# MCU.net
KiCad netlist of a schematic drawn in Altium Designer
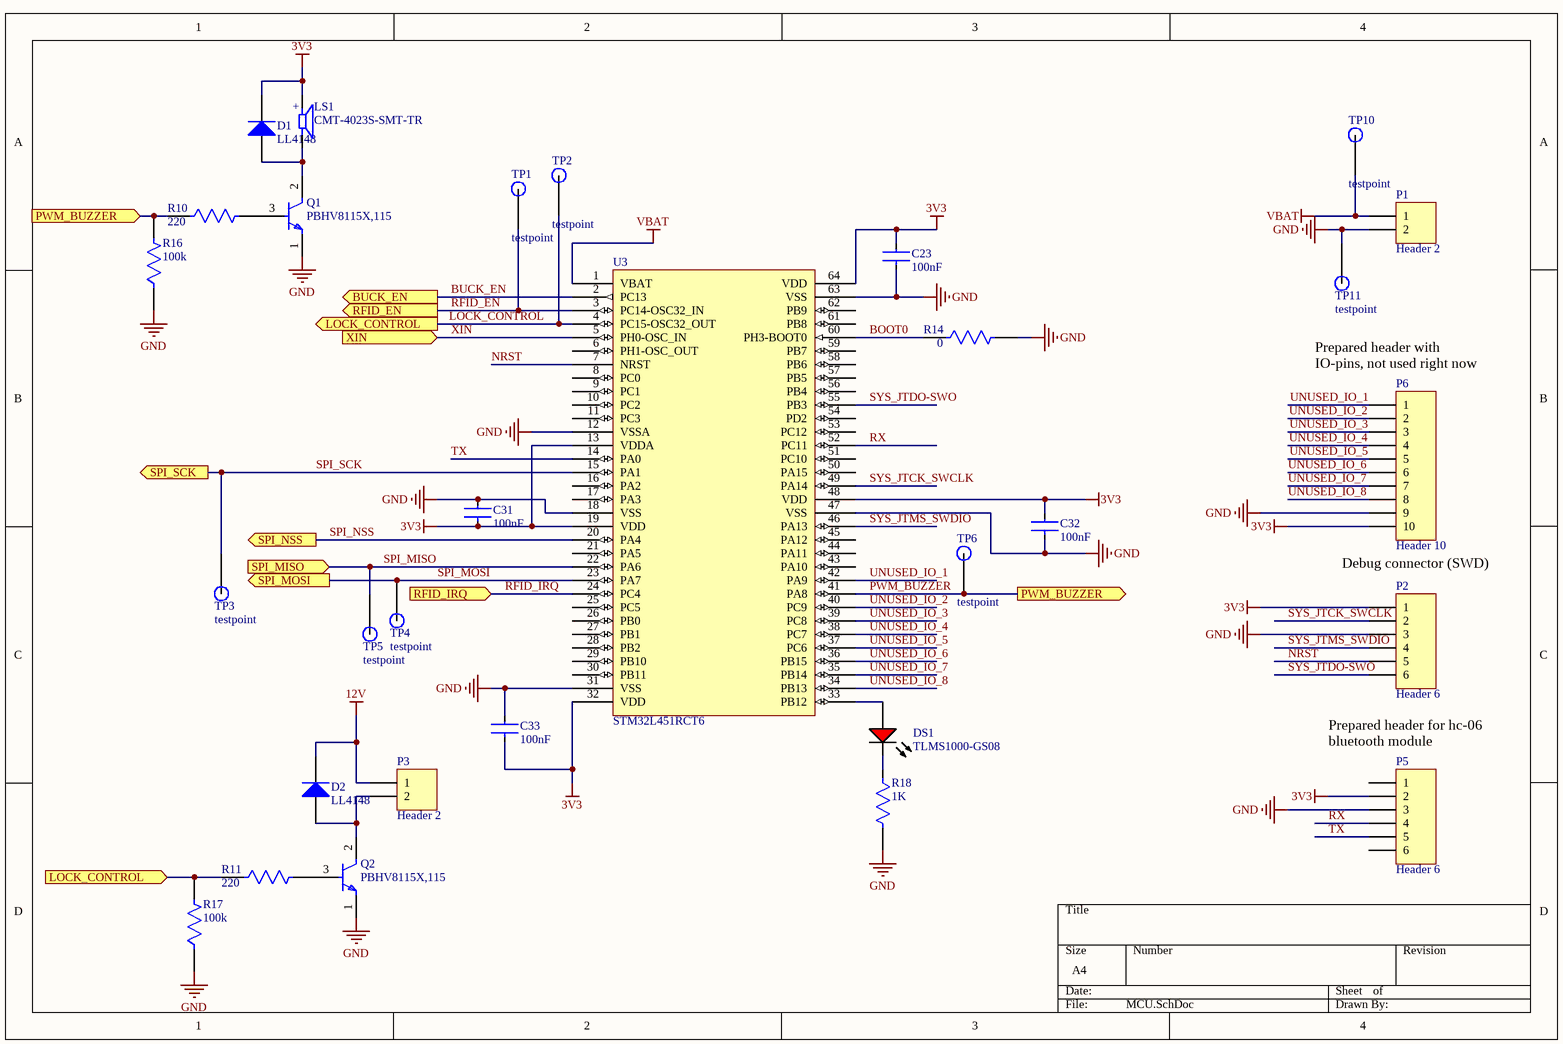
[diagram p0: MCU.SchDoc]

(export (version "E")
  (design (tool "Eeschema 10.0.6"))
  (components
    (comp (ref "C23")
      (value "100nF")
      (footprint "FP-GCJ21B-0_3-IPC_A")
      (description "Multilayer Ceramic Capacitors MLCC - SMD/SMT 0805 2.2uF 10%, 16VDC,  X7R 15%")
      (fields (field (name "TOLERANCE") "10%"))
      (libsource (lib "Altium Content Vault") (part "02cd4be3c70576c341d710602a673aa"))
    )
    (comp (ref "C31")
      (value "100nF")
      (footprint "FP-GCJ21B-0_3-IPC_A")
      (description "Multilayer Ceramic Capacitors MLCC - SMD/SMT 0805 2.2uF 10%, 16VDC,  X7R 15%")
      (fields (field (name "TOLERANCE") "10%"))
      (libsource (lib "Altium Content Vault") (part "02cd4be3c70576c341d710602a673aa"))
    )
    (comp (ref "C32")
      (value "100nF")
      (footprint "FP-GCJ21B-0_3-IPC_A")
      (description "Multilayer Ceramic Capacitors MLCC - SMD/SMT 0805 2.2uF 10%, 16VDC,  X7R 15%")
      (fields (field (name "TOLERANCE") "10%"))
      (libsource (lib "Altium Content Vault") (part "02cd4be3c70576c341d710602a673aa"))
    )
    (comp (ref "C33")
      (value "100nF")
      (footprint "FP-GCJ21B-0_3-IPC_A")
      (description "Multilayer Ceramic Capacitors MLCC - SMD/SMT 0805 2.2uF 10%, 16VDC,  X7R 15%")
      (fields (field (name "TOLERANCE") "10%"))
      (libsource (lib "Altium Content Vault") (part "02cd4be3c70576c341d710602a673aa"))
    )
    (comp (ref "D1")
      (value "LL4148")
      (footprint "FAIR-SOD80-2_V")
      (description "Small Signal Diode, 100 V, 0.2 A, -55 to 175 degC, 2-Pin SOD80, RoHS, Tape and Reel")
      (fields (field (name "MANUFACTURER") "Fairchild"))
      (libsource (lib "Altium Content Vault") (part "D-AK-2"))
    )
    (comp (ref "D2")
      (value "LL4148")
      (footprint "FAIR-SOD80-2_V")
      (description "Small Signal Diode, 100 V, 0.2 A, -55 to 175 degC, 2-Pin SOD80, RoHS, Tape and Reel")
      (fields (field (name "MANUFACTURER") "Fairchild"))
      (libsource (lib "Altium Content Vault") (part "D-AK-2"))
    )
    (comp (ref "DS1")
      (value "TLMS1000-GS08")
      (footprint "VISH-TLMS1000_V")
      (description "Low Current LED, 40 mW, 1.8 V, -40 to 100 degC, 2-Pin SMD (0603), RoHS, Tape and Reel")
      (fields (field (name "MANUFACTURER") "Vishay"))
      (libsource (lib "Altium Content Vault") (part "LED-RED-AK-2"))
    )
    (comp (ref "LS1")
      (value "CMT-4023S-SMT-TR")
      (footprint "CUI_CMT-4023S-SMT-TR")
      (description "4 mm, 3 Vo-p, 70 dB, Surface Mount _SMT_, Magnetic Audio Transducer Buzzer")
      (fields (field (name "MF") "CUI Devices"))
      (libsource (lib "Schlib") (part "CMT-4023S-SMT-TR"))
    )
    (comp (ref "P1")
      (value "Header 2")
      (footprint "HDR1X2")
      (description "Header, 2-Pin")
      (fields (field (name "PUBLISHER") "Altium Limited"))
      (libsource (lib "Miscellaneous Connectors") (part "Header 2"))
    )
    (comp (ref "P2")
      (value "Header 6")
      (footprint "HDR1X6")
      (description "Header, 6-Pin")
      (fields (field (name "PUBLISHER") "Altium Limited"))
      (libsource (lib "Miscellaneous Connectors") (part "Header 6"))
    )
    (comp (ref "P3")
      (value "Header 2")
      (footprint "HDR1X2")
      (description "Header, 2-Pin")
      (fields (field (name "PUBLISHER") "Altium Limited"))
      (libsource (lib "Miscellaneous Connectors") (part "Header 2"))
    )
    (comp (ref "P5")
      (value "Header 6")
      (footprint "HDR1X6")
      (description "Header, 6-Pin")
      (fields (field (name "PUBLISHER") "Altium Limited"))
      (libsource (lib "Miscellaneous Connectors") (part "Header 6"))
    )
    (comp (ref "P6")
      (value "Header 10")
      (footprint "HDR1X10")
      (description "Header, 10-Pin")
      (fields (field (name "PUBLISHER") "Altium Limited"))
      (libsource (lib "Miscellaneous Connectors") (part "Header 10"))
    )
    (comp (ref "Q1")
      (value "PBHV8115X,115")
      (footprint "FP-SOT89-MFG")
      (description "TRANS NPN 150V 1A SOT89")
      (fields
        (field (name "MANUFACTURER") "Nexperia")
        (field (name "OCTOPART") "https://octopart.com/pbhv8115x%2C115-nexperia-78740688")
      )
      (libsource (lib "Altium Content Vault") (part "22d2bcc0fe72a7c4622b2c6aaace23d"))
    )
    (comp (ref "Q2")
      (value "PBHV8115X,115")
      (footprint "FP-SOT89-MFG")
      (description "TRANS NPN 150V 1A SOT89")
      (fields
        (field (name "MANUFACTURER") "Nexperia")
        (field (name "OCTOPART") "https://octopart.com/pbhv8115x%2C115-nexperia-78740688")
      )
      (libsource (lib "Altium Content Vault") (part "22d2bcc0fe72a7c4622b2c6aaace23d"))
    )
    (comp (ref "R10")
      (value "220")
      (footprint "FP-AC0603-MFG")
      (description "RES SMD 60.4 OHM 1% 1/10W 0603")
      (fields
        (field (name "MANUFACTURER PART NUMBER") "AC0603FR-0760R4L")
        (field (name "OCTOPART") "https://octopart.com/ac0603fr-0760r4l-yageo-71367350")
      )
      (libsource (lib "Altium Content Vault") (part "1029c3af85768c4190bb7ad29bc67b5"))
    )
    (comp (ref "R11")
      (value "220")
      (footprint "FP-AC0603-MFG")
      (description "RES SMD 60.4 OHM 1% 1/10W 0603")
      (fields
        (field (name "MANUFACTURER PART NUMBER") "AC0603FR-0760R4L")
        (field (name "OCTOPART") "https://octopart.com/ac0603fr-0760r4l-yageo-71367350")
      )
      (libsource (lib "Altium Content Vault") (part "1029c3af85768c4190bb7ad29bc67b5"))
    )
    (comp (ref "R14")
      (value "0")
      (footprint "FP-AC0603-MFG")
      (description "RES SMD 60.4 OHM 1% 1/10W 0603")
      (fields
        (field (name "MANUFACTURER PART NUMBER") "AC0603FR-0760R4L")
        (field (name "OCTOPART") "https://octopart.com/ac0603fr-0760r4l-yageo-71367350")
      )
      (libsource (lib "Altium Content Vault") (part "1029c3af85768c4190bb7ad29bc67b5"))
    )
    (comp (ref "R16")
      (value "100k")
      (footprint "FP-AC0603-MFG")
      (description "RES SMD 60.4 OHM 1% 1/10W 0603")
      (fields
        (field (name "MANUFACTURER PART NUMBER") "AC0603FR-0760R4L")
        (field (name "OCTOPART") "https://octopart.com/ac0603fr-0760r4l-yageo-71367350")
      )
      (libsource (lib "Altium Content Vault") (part "1029c3af85768c4190bb7ad29bc67b5"))
    )
    (comp (ref "R17")
      (value "100k")
      (footprint "FP-AC0603-MFG")
      (description "RES SMD 60.4 OHM 1% 1/10W 0603")
      (fields
        (field (name "MANUFACTURER PART NUMBER") "AC0603FR-0760R4L")
        (field (name "OCTOPART") "https://octopart.com/ac0603fr-0760r4l-yageo-71367350")
      )
      (libsource (lib "Altium Content Vault") (part "1029c3af85768c4190bb7ad29bc67b5"))
    )
    (comp (ref "R18")
      (value "1K")
      (footprint "FP-AC0603-MFG")
      (description "RES SMD 60.4 OHM 1% 1/10W 0603")
      (fields
        (field (name "MANUFACTURER PART NUMBER") "AC0603FR-0760R4L")
        (field (name "OCTOPART") "https://octopart.com/ac0603fr-0760r4l-yageo-71367350")
      )
      (libsource (lib "Altium Content Vault") (part "1029c3af85768c4190bb7ad29bc67b5"))
    )
    (comp (ref "TP1")
      (value "testpoint")
      (footprint "Testpoint")
      (libsource (lib "Schlib") (part "testpoint"))
    )
    (comp (ref "TP2")
      (value "testpoint")
      (footprint "Testpoint")
      (libsource (lib "Schlib") (part "testpoint"))
    )
    (comp (ref "TP3")
      (value "testpoint")
      (footprint "Testpoint")
      (libsource (lib "Schlib") (part "testpoint"))
    )
    (comp (ref "TP4")
      (value "testpoint")
      (footprint "Testpoint")
      (libsource (lib "Schlib") (part "testpoint"))
    )
    (comp (ref "TP5")
      (value "testpoint")
      (footprint "Testpoint")
      (libsource (lib "Schlib") (part "testpoint"))
    )
    (comp (ref "TP6")
      (value "testpoint")
      (footprint "Testpoint")
      (libsource (lib "Schlib") (part "testpoint"))
    )
    (comp (ref "TP10")
      (value "testpoint")
      (footprint "Testpoint")
      (libsource (lib "Schlib") (part "testpoint"))
    )
    (comp (ref "TP11")
      (value "testpoint")
      (footprint "Testpoint")
      (libsource (lib "Schlib") (part "testpoint"))
    )
    (comp (ref "U3")
      (value "STM32L451RCT6")
      (footprint "LQFP-64")
      (description "MCU 32-bit STM32")
      (fields (field (name "MANUFACTURER") "STMicroelectronics"))
      (libsource (lib "Schlib") (part "STM32L451RCT6"))
    )
  )
  (nets
    (net (code "1") (name "/BOOT0") (class "Default")
      (node (ref "R14") (pin "1") (pinfunction "1_1") (pintype "passive"))
      (node (ref "U3") (pin "60") (pinfunction "PH3-BOOT0_60") (pintype "input"))
    )
    (net (code "2") (name "/BUCK_EN") (class "Default")
      (node (ref "U3") (pin "2") (pinfunction "PC13_2") (pintype "output"))
    )
    (net (code "3") (name "/LOCK_CONTROL") (class "Default")
      (node (ref "R11") (pin "1") (pinfunction "1_1") (pintype "passive"))
      (node (ref "R17") (pin "2") (pinfunction "2_2") (pintype "passive"))
      (node (ref "TP2") (pin "1") (pinfunction "tp_1") (pintype "passive"))
      (node (ref "U3") (pin "4") (pinfunction "PC15-OSC32_OUT_4") (pintype "bidirectional"))
    )
    (net (code "4") (name "/NRST") (class "Default")
      (node (ref "P2") (pin "5") (pinfunction "5_5") (pintype "passive"))
      (node (ref "U3") (pin "7") (pinfunction "NRST_7") (pintype "passive"))
    )
    (net (code "5") (name "/PWM_BUZZER") (class "Default")
      (node (ref "R10") (pin "1") (pinfunction "1_1") (pintype "passive"))
      (node (ref "R16") (pin "2") (pinfunction "2_2") (pintype "passive"))
      (node (ref "TP6") (pin "1") (pinfunction "tp_1") (pintype "passive"))
      (node (ref "U3") (pin "41") (pinfunction "PA8_41") (pintype "bidirectional"))
    )
    (net (code "6") (name "/RFID_EN") (class "Default")
      (node (ref "TP1") (pin "1") (pinfunction "tp_1") (pintype "passive"))
      (node (ref "U3") (pin "3") (pinfunction "PC14-OSC32_IN_3") (pintype "bidirectional"))
    )
    (net (code "7") (name "/RFID_IRQ") (class "Default")
      (node (ref "U3") (pin "24") (pinfunction "PC4_24") (pintype "bidirectional"))
    )
    (net (code "8") (name "/RX") (class "Default")
      (node (ref "P5") (pin "4") (pinfunction "4_4") (pintype "passive"))
      (node (ref "U3") (pin "52") (pinfunction "PC11_52") (pintype "bidirectional"))
    )
    (net (code "9") (name "/SPI_MISO") (class "Default")
      (node (ref "TP5") (pin "1") (pinfunction "tp_1") (pintype "passive"))
      (node (ref "U3") (pin "22") (pinfunction "PA6_22") (pintype "bidirectional"))
    )
    (net (code "10") (name "/SPI_MOSI") (class "Default")
      (node (ref "TP4") (pin "1") (pinfunction "tp_1") (pintype "passive"))
      (node (ref "U3") (pin "23") (pinfunction "PA7_23") (pintype "bidirectional"))
    )
    (net (code "11") (name "/SPI_NSS") (class "Default")
      (node (ref "U3") (pin "20") (pinfunction "PA4_20") (pintype "bidirectional"))
    )
    (net (code "12") (name "/SPI_SCK") (class "Default")
      (node (ref "TP3") (pin "1") (pinfunction "tp_1") (pintype "passive"))
      (node (ref "U3") (pin "15") (pinfunction "PA1_15") (pintype "bidirectional"))
    )
    (net (code "13") (name "/SYS_JTCK_SWCLK") (class "Default")
      (node (ref "P2") (pin "2") (pinfunction "2_2") (pintype "passive"))
      (node (ref "U3") (pin "49") (pinfunction "PA14_49") (pintype "bidirectional"))
    )
    (net (code "14") (name "/SYS_JTDO-SWO") (class "Default")
      (node (ref "P2") (pin "6") (pinfunction "6_6") (pintype "passive"))
      (node (ref "U3") (pin "55") (pinfunction "PB3_55") (pintype "bidirectional"))
    )
    (net (code "15") (name "/SYS_JTMS_SWDIO") (class "Default")
      (node (ref "P2") (pin "4") (pinfunction "4_4") (pintype "passive"))
      (node (ref "U3") (pin "46") (pinfunction "PA13_46") (pintype "bidirectional"))
    )
    (net (code "16") (name "/TX") (class "Default")
      (node (ref "P5") (pin "5") (pinfunction "5_5") (pintype "passive"))
      (node (ref "U3") (pin "14") (pinfunction "PA0_14") (pintype "bidirectional"))
    )
    (net (code "17") (name "/UNUSED_IO_1") (class "Default")
      (node (ref "P6") (pin "1") (pinfunction "1_1") (pintype "passive"))
      (node (ref "U3") (pin "42") (pinfunction "PA9_42") (pintype "bidirectional"))
    )
    (net (code "18") (name "/UNUSED_IO_2") (class "Default")
      (node (ref "P6") (pin "2") (pinfunction "2_2") (pintype "passive"))
      (node (ref "U3") (pin "40") (pinfunction "PC9_40") (pintype "bidirectional"))
    )
    (net (code "19") (name "/UNUSED_IO_3") (class "Default")
      (node (ref "P6") (pin "3") (pinfunction "3_3") (pintype "passive"))
      (node (ref "U3") (pin "39") (pinfunction "PC8_39") (pintype "bidirectional"))
    )
    (net (code "20") (name "/UNUSED_IO_4") (class "Default")
      (node (ref "P6") (pin "4") (pinfunction "4_4") (pintype "passive"))
      (node (ref "U3") (pin "38") (pinfunction "PC7_38") (pintype "bidirectional"))
    )
    (net (code "21") (name "/UNUSED_IO_5") (class "Default")
      (node (ref "P6") (pin "5") (pinfunction "5_5") (pintype "passive"))
      (node (ref "U3") (pin "37") (pinfunction "PC6_37") (pintype "bidirectional"))
    )
    (net (code "22") (name "/UNUSED_IO_6") (class "Default")
      (node (ref "P6") (pin "6") (pinfunction "6_6") (pintype "passive"))
      (node (ref "U3") (pin "36") (pinfunction "PB15_36") (pintype "bidirectional"))
    )
    (net (code "23") (name "/UNUSED_IO_7") (class "Default")
      (node (ref "P6") (pin "7") (pinfunction "7_7") (pintype "passive"))
      (node (ref "U3") (pin "35") (pinfunction "PB14_35") (pintype "bidirectional"))
    )
    (net (code "24") (name "/UNUSED_IO_8") (class "Default")
      (node (ref "P6") (pin "8") (pinfunction "8_8") (pintype "passive"))
      (node (ref "U3") (pin "34") (pinfunction "PB13_34") (pintype "bidirectional"))
    )
    (net (code "25") (name "/XIN") (class "Default")
      (node (ref "U3") (pin "5") (pinfunction "PH0-OSC_IN_5") (pintype "bidirectional"))
    )
    (net (code "26") (name "3V3") (class "Default")
      (node (ref "C23") (pin "2") (pinfunction "2_2") (pintype "passive"))
      (node (ref "C31") (pin "1") (pinfunction "1_1") (pintype "passive"))
      (node (ref "C32") (pin "2") (pinfunction "2_2") (pintype "passive"))
      (node (ref "C33") (pin "1") (pinfunction "1_1") (pintype "passive"))
      (node (ref "D1") (pin "2") (pinfunction "K_2") (pintype "passive"))
      (node (ref "LS1") (pin "P") (pinfunction "P_P") (pintype "passive"))
      (node (ref "P2") (pin "1") (pinfunction "1_1") (pintype "passive"))
      (node (ref "P5") (pin "2") (pinfunction "2_2") (pintype "passive"))
      (node (ref "P6") (pin "10") (pinfunction "10_10") (pintype "passive"))
      (node (ref "U3") (pin "13") (pinfunction "VDDA_13") (pintype "power_in"))
      (node (ref "U3") (pin "19") (pinfunction "VDD_19") (pintype "power_in"))
      (node (ref "U3") (pin "32") (pinfunction "VDD_32") (pintype "power_in"))
      (node (ref "U3") (pin "48") (pinfunction "VDD_48") (pintype "power_in"))
      (node (ref "U3") (pin "64") (pinfunction "VDD_64") (pintype "power_in"))
    )
    (net (code "27") (name "12V") (class "Default")
      (node (ref "D2") (pin "2") (pinfunction "K_2") (pintype "passive"))
      (node (ref "P3") (pin "1") (pinfunction "1_1") (pintype "passive"))
    )
    (net (code "28") (name "GND") (class "Default")
      (node (ref "C23") (pin "1") (pinfunction "1_1") (pintype "passive"))
      (node (ref "C31") (pin "2") (pinfunction "2_2") (pintype "passive"))
      (node (ref "C32") (pin "1") (pinfunction "1_1") (pintype "passive"))
      (node (ref "C33") (pin "2") (pinfunction "2_2") (pintype "passive"))
      (node (ref "P1") (pin "2") (pinfunction "2_2") (pintype "passive"))
      (node (ref "P2") (pin "3") (pinfunction "3_3") (pintype "passive"))
      (node (ref "P5") (pin "3") (pinfunction "3_3") (pintype "passive"))
      (node (ref "P6") (pin "9") (pinfunction "9_9") (pintype "passive"))
      (node (ref "Q1") (pin "1") (pinfunction "E_1") (pintype "passive"))
      (node (ref "Q2") (pin "1") (pinfunction "E_1") (pintype "passive"))
      (node (ref "R14") (pin "2") (pinfunction "2_2") (pintype "passive"))
      (node (ref "R16") (pin "1") (pinfunction "1_1") (pintype "passive"))
      (node (ref "R17") (pin "1") (pinfunction "1_1") (pintype "passive"))
      (node (ref "R18") (pin "2") (pinfunction "2_2") (pintype "passive"))
      (node (ref "TP11") (pin "1") (pinfunction "tp_1") (pintype "passive"))
      (node (ref "U3") (pin "12") (pinfunction "VSSA_12") (pintype "power_in"))
      (node (ref "U3") (pin "18") (pinfunction "VSS_18") (pintype "power_in"))
      (node (ref "U3") (pin "31") (pinfunction "VSS_31") (pintype "power_in"))
      (node (ref "U3") (pin "47") (pinfunction "VSS_47") (pintype "power_in"))
      (node (ref "U3") (pin "63") (pinfunction "VSS_63") (pintype "power_in"))
    )
    (net (code "29") (name "Net-(D1-A)") (class "Default")
      (node (ref "D1") (pin "1") (pinfunction "A_1") (pintype "passive"))
      (node (ref "LS1") (pin "N") (pinfunction "N_N") (pintype "passive"))
      (node (ref "Q1") (pin "2") (pinfunction "C_2") (pintype "passive"))
    )
    (net (code "30") (name "Net-(D2-A)") (class "Default")
      (node (ref "D2") (pin "1") (pinfunction "A_1") (pintype "passive"))
      (node (ref "P3") (pin "2") (pinfunction "2_2") (pintype "passive"))
      (node (ref "Q2") (pin "2") (pinfunction "C_2") (pintype "passive"))
    )
    (net (code "31") (name "Net-(DS1-A)") (class "Default")
      (node (ref "DS1") (pin "1") (pinfunction "A_1") (pintype "passive"))
      (node (ref "U3") (pin "33") (pinfunction "PB12_33") (pintype "bidirectional"))
    )
    (net (code "32") (name "Net-(DS1-K)") (class "Default")
      (node (ref "DS1") (pin "2") (pinfunction "K_2") (pintype "passive"))
      (node (ref "R18") (pin "1") (pinfunction "1_1") (pintype "passive"))
    )
    (net (code "33") (name "Net-(Q1-B)") (class "Default")
      (node (ref "Q1") (pin "3") (pinfunction "B_3") (pintype "passive"))
      (node (ref "R10") (pin "2") (pinfunction "2_2") (pintype "passive"))
    )
    (net (code "34") (name "Net-(Q2-B)") (class "Default")
      (node (ref "Q2") (pin "3") (pinfunction "B_3") (pintype "passive"))
      (node (ref "R11") (pin "2") (pinfunction "2_2") (pintype "passive"))
    )
    (net (code "35") (name "VBAT") (class "Default")
      (node (ref "P1") (pin "1") (pinfunction "1_1") (pintype "passive"))
      (node (ref "TP10") (pin "1") (pinfunction "tp_1") (pintype "passive"))
      (node (ref "U3") (pin "1") (pinfunction "VBAT_1") (pintype "power_in"))
    )
    (net (code "36") (name "unconnected-(P5-Pad1)") (class "Default")
      (node (ref "P5") (pin "1") (pinfunction "1_1") (pintype "passive"))
    )
    (net (code "37") (name "unconnected-(P5-Pad6)") (class "Default")
      (node (ref "P5") (pin "6") (pinfunction "6_6") (pintype "passive"))
    )
    (net (code "38") (name "unconnected-(U3-PA2-Pad16)") (class "Default")
      (node (ref "U3") (pin "16") (pinfunction "PA2_16") (pintype "bidirectional"))
    )
    (net (code "39") (name "unconnected-(U3-PA3-Pad17)") (class "Default")
      (node (ref "U3") (pin "17") (pinfunction "PA3_17") (pintype "bidirectional"))
    )
    (net (code "40") (name "unconnected-(U3-PA5-Pad21)") (class "Default")
      (node (ref "U3") (pin "21") (pinfunction "PA5_21") (pintype "bidirectional"))
    )
    (net (code "41") (name "unconnected-(U3-PA10-Pad43)") (class "Default")
      (node (ref "U3") (pin "43") (pinfunction "PA10_43") (pintype "bidirectional"))
    )
    (net (code "42") (name "unconnected-(U3-PA11-Pad44)") (class "Default")
      (node (ref "U3") (pin "44") (pinfunction "PA11_44") (pintype "bidirectional"))
    )
    (net (code "43") (name "unconnected-(U3-PA12-Pad45)") (class "Default")
      (node (ref "U3") (pin "45") (pinfunction "PA12_45") (pintype "bidirectional"))
    )
    (net (code "44") (name "unconnected-(U3-PA15-Pad50)") (class "Default")
      (node (ref "U3") (pin "50") (pinfunction "PA15_50") (pintype "bidirectional"))
    )
    (net (code "45") (name "unconnected-(U3-PB0-Pad26)") (class "Default")
      (node (ref "U3") (pin "26") (pinfunction "PB0_26") (pintype "bidirectional"))
    )
    (net (code "46") (name "unconnected-(U3-PB1-Pad27)") (class "Default")
      (node (ref "U3") (pin "27") (pinfunction "PB1_27") (pintype "bidirectional"))
    )
    (net (code "47") (name "unconnected-(U3-PB2-Pad28)") (class "Default")
      (node (ref "U3") (pin "28") (pinfunction "PB2_28") (pintype "bidirectional"))
    )
    (net (code "48") (name "unconnected-(U3-PB4-Pad56)") (class "Default")
      (node (ref "U3") (pin "56") (pinfunction "PB4_56") (pintype "bidirectional"))
    )
    (net (code "49") (name "unconnected-(U3-PB5-Pad57)") (class "Default")
      (node (ref "U3") (pin "57") (pinfunction "PB5_57") (pintype "bidirectional"))
    )
    (net (code "50") (name "unconnected-(U3-PB6-Pad58)") (class "Default")
      (node (ref "U3") (pin "58") (pinfunction "PB6_58") (pintype "bidirectional"))
    )
    (net (code "51") (name "unconnected-(U3-PB7-Pad59)") (class "Default")
      (node (ref "U3") (pin "59") (pinfunction "PB7_59") (pintype "bidirectional"))
    )
    (net (code "52") (name "unconnected-(U3-PB8-Pad61)") (class "Default")
      (node (ref "U3") (pin "61") (pinfunction "PB8_61") (pintype "bidirectional"))
    )
    (net (code "53") (name "unconnected-(U3-PB9-Pad62)") (class "Default")
      (node (ref "U3") (pin "62") (pinfunction "PB9_62") (pintype "bidirectional"))
    )
    (net (code "54") (name "unconnected-(U3-PB10-Pad29)") (class "Default")
      (node (ref "U3") (pin "29") (pinfunction "PB10_29") (pintype "bidirectional"))
    )
    (net (code "55") (name "unconnected-(U3-PB11-Pad30)") (class "Default")
      (node (ref "U3") (pin "30") (pinfunction "PB11_30") (pintype "bidirectional"))
    )
    (net (code "56") (name "unconnected-(U3-PC0-Pad8)") (class "Default")
      (node (ref "U3") (pin "8") (pinfunction "PC0_8") (pintype "bidirectional"))
    )
    (net (code "57") (name "unconnected-(U3-PC1-Pad9)") (class "Default")
      (node (ref "U3") (pin "9") (pinfunction "PC1_9") (pintype "bidirectional"))
    )
    (net (code "58") (name "unconnected-(U3-PC2-Pad10)") (class "Default")
      (node (ref "U3") (pin "10") (pinfunction "PC2_10") (pintype "bidirectional"))
    )
    (net (code "59") (name "unconnected-(U3-PC3-Pad11)") (class "Default")
      (node (ref "U3") (pin "11") (pinfunction "PC3_11") (pintype "bidirectional"))
    )
    (net (code "60") (name "unconnected-(U3-PC5-Pad25)") (class "Default")
      (node (ref "U3") (pin "25") (pinfunction "PC5_25") (pintype "bidirectional"))
    )
    (net (code "61") (name "unconnected-(U3-PC10-Pad51)") (class "Default")
      (node (ref "U3") (pin "51") (pinfunction "PC10_51") (pintype "bidirectional"))
    )
    (net (code "62") (name "unconnected-(U3-PC12-Pad53)") (class "Default")
      (node (ref "U3") (pin "53") (pinfunction "PC12_53") (pintype "bidirectional"))
    )
    (net (code "63") (name "unconnected-(U3-PD2-Pad54)") (class "Default")
      (node (ref "U3") (pin "54") (pinfunction "PD2_54") (pintype "bidirectional"))
    )
    (net (code "64") (name "unconnected-(U3-PH1-OSC_OUT-Pad6)") (class "Default")
      (node (ref "U3") (pin "6") (pinfunction "PH1-OSC_OUT_6") (pintype "bidirectional"))
    )
  )
)
